# Sense_1_Signal_Isolation.net
KiCad netlist of a schematic drawn in Altium Designer
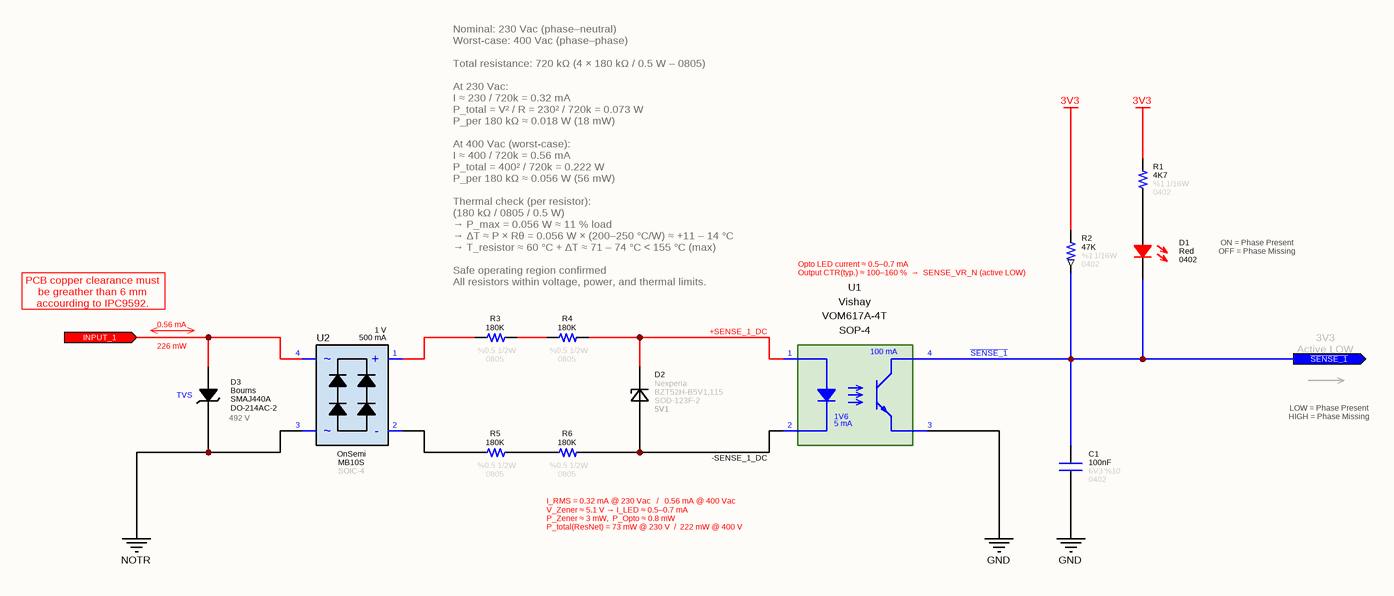
[diagram p0: Sense 1 Signal Isolation.SchDoc]

(export (version "E")
  (design (tool "Eeschema 10.0.6"))
  (components
    (comp (ref "C1")
      (value "100nF")
      (footprint "CAPACITOR_0402")
      (description "Capacitor (MLCC) - 100nF / 6V3 / 0402")
      (fields
        (field (name "MANUFACTURER PART NUMBER") "04026D104KAT4A")
        (field (name "TOLERANCE") "%10")
        (field (name "VOLTAGE") "6V3")
        (field (name "CASE") "0402")
        (field (name "Comment") "Capacitor - 100nF [0402] (MLCC)")
      )
      (libsource (lib "Akkoyun") (part "Capacitor - 100nF [0402-6V3]"))
    )
    (comp (ref "D1")
      (value "SMD LED (Red)")
      (footprint "LED_0402")
      (description "Standard LEDs - SMD MINI-MOLD ULTRA COMPACT RED")
      (fields
        (field (name "MANUFACTURER PART NUMBER") "SML-P12VTT86R")
        (field (name "CASE") "0402")
        (field (name "COLOR") "Red")
      )
      (libsource (lib "Akkoyun") (part "Diode - LED (0402-Red)"))
    )
    (comp (ref "D2")
      (value "BZT52H-B5V1,115")
      (footprint "SOD-123F-2")
      (description "Zener Diodes BZT52H-B5V1/SOD123F/SOD2")
      (fields
        (field (name "ZENER VOLTAGE") "5V1")
        (field (name "MANUFACTURER NAME") "Nexperia")
        (field (name "MANUFACTURER PART NUMBER") "BZT52H-B5V1,115")
        (field (name "CASE") "SOD-123F-2")
      )
      (libsource (lib "Akkoyun") (part "Diode - BZT52H-B5V1,115"))
    )
    (comp (ref "D3")
      (value "SMAJ440A")
      (footprint "DO-220AA-2")
      (description "ESD Protection Diodes / TVS Diodes 440volts 1uA .6 Amps Uni-Dir")
      (fields
        (field (name "BREAKDOWN VOLTAGE") "492 V")
        (field (name "MANUFACTURER NAME") "Bourns")
        (field (name "MANUFACTURER PART NUMBER") "SMAJ440A")
        (field (name "CASE") "DO-214AC-2")
      )
      (libsource (lib "Akkoyun") (part "Diode - SMAJ440A (TVS)"))
    )
    (comp (ref "R1")
      (value "4K7")
      (footprint "RESISTOR_0402")
      (description "Thick Film Resistors - SMD 1/16 W 4.7 KOhm 1%")
      (fields
        (field (name "MANUFACTURER PART NUMBER") "CRCW04024K70FKED")
        (field (name "TOLERANCE") "%1")
        (field (name "CASE") "0402")
        (field (name "POWER") "1/16W")
        (field (name "Comment") "4K7 - 0402 - %1 - 1/16W")
      )
      (libsource (lib "Akkoyun") (part "Resistor - 4K7 [0402]"))
    )
    (comp (ref "R2")
      (value "47K")
      (footprint "RESISTOR_0402")
      (description "Thick Film Resistors - SMD 1/16 W 47 KOhm 1%")
      (fields
        (field (name "MANUFACTURER PART NUMBER") "CRCW040247K0FKED")
        (field (name "TOLERANCE") "%1")
        (field (name "CASE") "0402")
        (field (name "POWER") "1/16W")
        (field (name "Comment") "47K - 0402 - %1 - 1/16W")
      )
      (libsource (lib "Akkoyun") (part "Resistor - 47K [0402]"))
    )
    (comp (ref "R3")
      (value "180K")
      (footprint "RESISTOR_0805")
      (description "Thick Film Resistors - SMD 0805 180Kohms 0.5W 0.5% AEC-Q200")
      (fields
        (field (name "MANUFACTURER PART NUMBER") "ERJ-P06D1803V")
        (field (name "TOLERANCE") "%0.5")
        (field (name "CASE") "0805")
        (field (name "POWER") "1/2W")
        (field (name "Comment") "180K - 0805 - %0.5 - 1/2W")
      )
      (libsource (lib "Akkoyun") (part "Resistor - 180K [0805]"))
    )
    (comp (ref "R4")
      (value "180K")
      (footprint "RESISTOR_0805")
      (description "Thick Film Resistors - SMD 0805 180Kohms 0.5W 0.5% AEC-Q200")
      (fields
        (field (name "MANUFACTURER PART NUMBER") "ERJ-P06D1803V")
        (field (name "TOLERANCE") "%0.5")
        (field (name "CASE") "0805")
        (field (name "POWER") "1/2W")
        (field (name "Comment") "180K - 0805 - %0.5 - 1/2W")
      )
      (libsource (lib "Akkoyun") (part "Resistor - 180K [0805]"))
    )
    (comp (ref "R5")
      (value "180K")
      (footprint "RESISTOR_0805")
      (description "Thick Film Resistors - SMD 0805 180Kohms 0.5W 0.5% AEC-Q200")
      (fields
        (field (name "MANUFACTURER PART NUMBER") "ERJ-P06D1803V")
        (field (name "TOLERANCE") "%0.5")
        (field (name "CASE") "0805")
        (field (name "POWER") "1/2W")
        (field (name "Comment") "180K - 0805 - %0.5 - 1/2W")
      )
      (libsource (lib "Akkoyun") (part "Resistor - 180K [0805]"))
    )
    (comp (ref "R6")
      (value "180K")
      (footprint "RESISTOR_0805")
      (description "Thick Film Resistors - SMD 0805 180Kohms 0.5W 0.5% AEC-Q200")
      (fields
        (field (name "MANUFACTURER PART NUMBER") "ERJ-P06D1803V")
        (field (name "TOLERANCE") "%0.5")
        (field (name "CASE") "0805")
        (field (name "POWER") "1/2W")
        (field (name "Comment") "180K - 0805 - %0.5 - 1/2W")
      )
      (libsource (lib "Akkoyun") (part "Resistor - 180K [0805]"))
    )
    (comp (ref "U1")
      (value "VOM617A-4T")
      (footprint "SOP-4V2")
      (description "Transistor Output Optocouplers Phototransistor Out CTR 160-320% 5mA")
      (fields
        (field (name "MANUFACTURER PART NUMBER") "VOM617A-4T")
        (field (name "MANUFACTURER NAME") "Vishay")
        (field (name "CASE") "SOP-4")
        (field (name "IF - FORWARD CURRENT") "5 mA")
        (field (name "VF - FORWARD VOLTAGE") "1V6")
        (field (name "MAXIMUM COLLECTOR CURRENT") "100 mA")
      )
      (libsource (lib "Akkoyun") (part "IC - VOM617A"))
    )
    (comp (ref "U2")
      (value "LTV-846S")
      (footprint "SOIC-4")
      (description "Transistor Output Optocouplers Optocplr Phototrans 4-Channel")
      (fields
        (field (name "IF - FORWARD CURRENT") "500 mA")
        (field (name "VF - FORWARD VOLTAGE") "1 V")
        (field (name "MANUFACTURER NAME") "OnSemi")
        (field (name "MANUFACTURER PART NUMBER") "MB10S")
        (field (name "CASE") "SOIC-4")
      )
      (libsource (lib "Akkoyun") (part "IC - MB10S"))
    )
  )
  (nets
    (net (code "1") (name "/+SENSE_1_DC") (class "Default")
      (node (ref "D2") (pin "1") (pinfunction "Cathode_1") (pintype "passive"))
      (node (ref "R4") (pin "1") (pinfunction "1_1") (pintype "passive"))
      (node (ref "U1") (pin "1") (pinfunction "LED_Anode_1") (pintype "passive"))
    )
    (net (code "2") (name "/-SENSE_1_DC") (class "Default")
      (node (ref "D2") (pin "2") (pinfunction "Anode_2") (pintype "passive"))
      (node (ref "R6") (pin "1") (pinfunction "1_1") (pintype "passive"))
      (node (ref "U1") (pin "2") (pinfunction "LED_Cathode_2") (pintype "passive"))
    )
    (net (code "3") (name "/INPUT_1") (class "Default")
      (node (ref "D3") (pin "1") (pinfunction "Anode_1") (pintype "passive"))
      (node (ref "U2") (pin "4") (pinfunction "~_4") (pintype "passive"))
    )
    (net (code "4") (name "/~{SENSE_1}") (class "Default")
      (node (ref "C1") (pin "2") (pinfunction "2_2") (pintype "passive"))
      (node (ref "D1") (pin "1") (pinfunction "1_1") (pintype "passive"))
      (node (ref "R2") (pin "1") (pinfunction "1_1") (pintype "output"))
      (node (ref "U1") (pin "4") (pinfunction "Collector_4") (pintype "passive"))
    )
    (net (code "5") (name "3V3") (class "Default")
      (node (ref "R1") (pin "2") (pinfunction "2_2") (pintype "passive"))
      (node (ref "R2") (pin "2") (pinfunction "2_2") (pintype "passive"))
    )
    (net (code "6") (name "GND") (class "Default")
      (node (ref "C1") (pin "1") (pinfunction "1_1") (pintype "passive"))
      (node (ref "U1") (pin "3") (pinfunction "Emiter_3") (pintype "passive"))
    )
    (net (code "7") (name "NOTR") (class "Default")
      (node (ref "D3") (pin "2") (pinfunction "Cathode_2") (pintype "passive"))
      (node (ref "U2") (pin "3") (pinfunction "~_3") (pintype "passive"))
    )
    (net (code "8") (name "Net-(D1-Pad2)") (class "Default")
      (node (ref "D1") (pin "2") (pinfunction "2_2") (pintype "passive"))
      (node (ref "R1") (pin "1") (pinfunction "1_1") (pintype "passive"))
    )
    (net (code "9") (name "Net-(R3-Pad1)") (class "Default")
      (node (ref "R3") (pin "1") (pinfunction "1_1") (pintype "passive"))
      (node (ref "R4") (pin "2") (pinfunction "2_2") (pintype "passive"))
    )
    (net (code "10") (name "Net-(R5-Pad1)") (class "Default")
      (node (ref "R5") (pin "1") (pinfunction "1_1") (pintype "passive"))
      (node (ref "R6") (pin "2") (pinfunction "2_2") (pintype "passive"))
    )
    (net (code "11") (name "Net-(U2-+)") (class "Default")
      (node (ref "R3") (pin "2") (pinfunction "2_2") (pintype "passive"))
      (node (ref "U2") (pin "1") (pinfunction "+_1") (pintype "passive"))
    )
    (net (code "12") (name "Net-(U2--)") (class "Default")
      (node (ref "R5") (pin "2") (pinfunction "2_2") (pintype "passive"))
      (node (ref "U2") (pin "2") (pinfunction "-_2") (pintype "passive"))
    )
  )
)
